# pca10090_sheet4_interface_mcu.net
KiCad netlist of a schematic drawn in Altium Designer
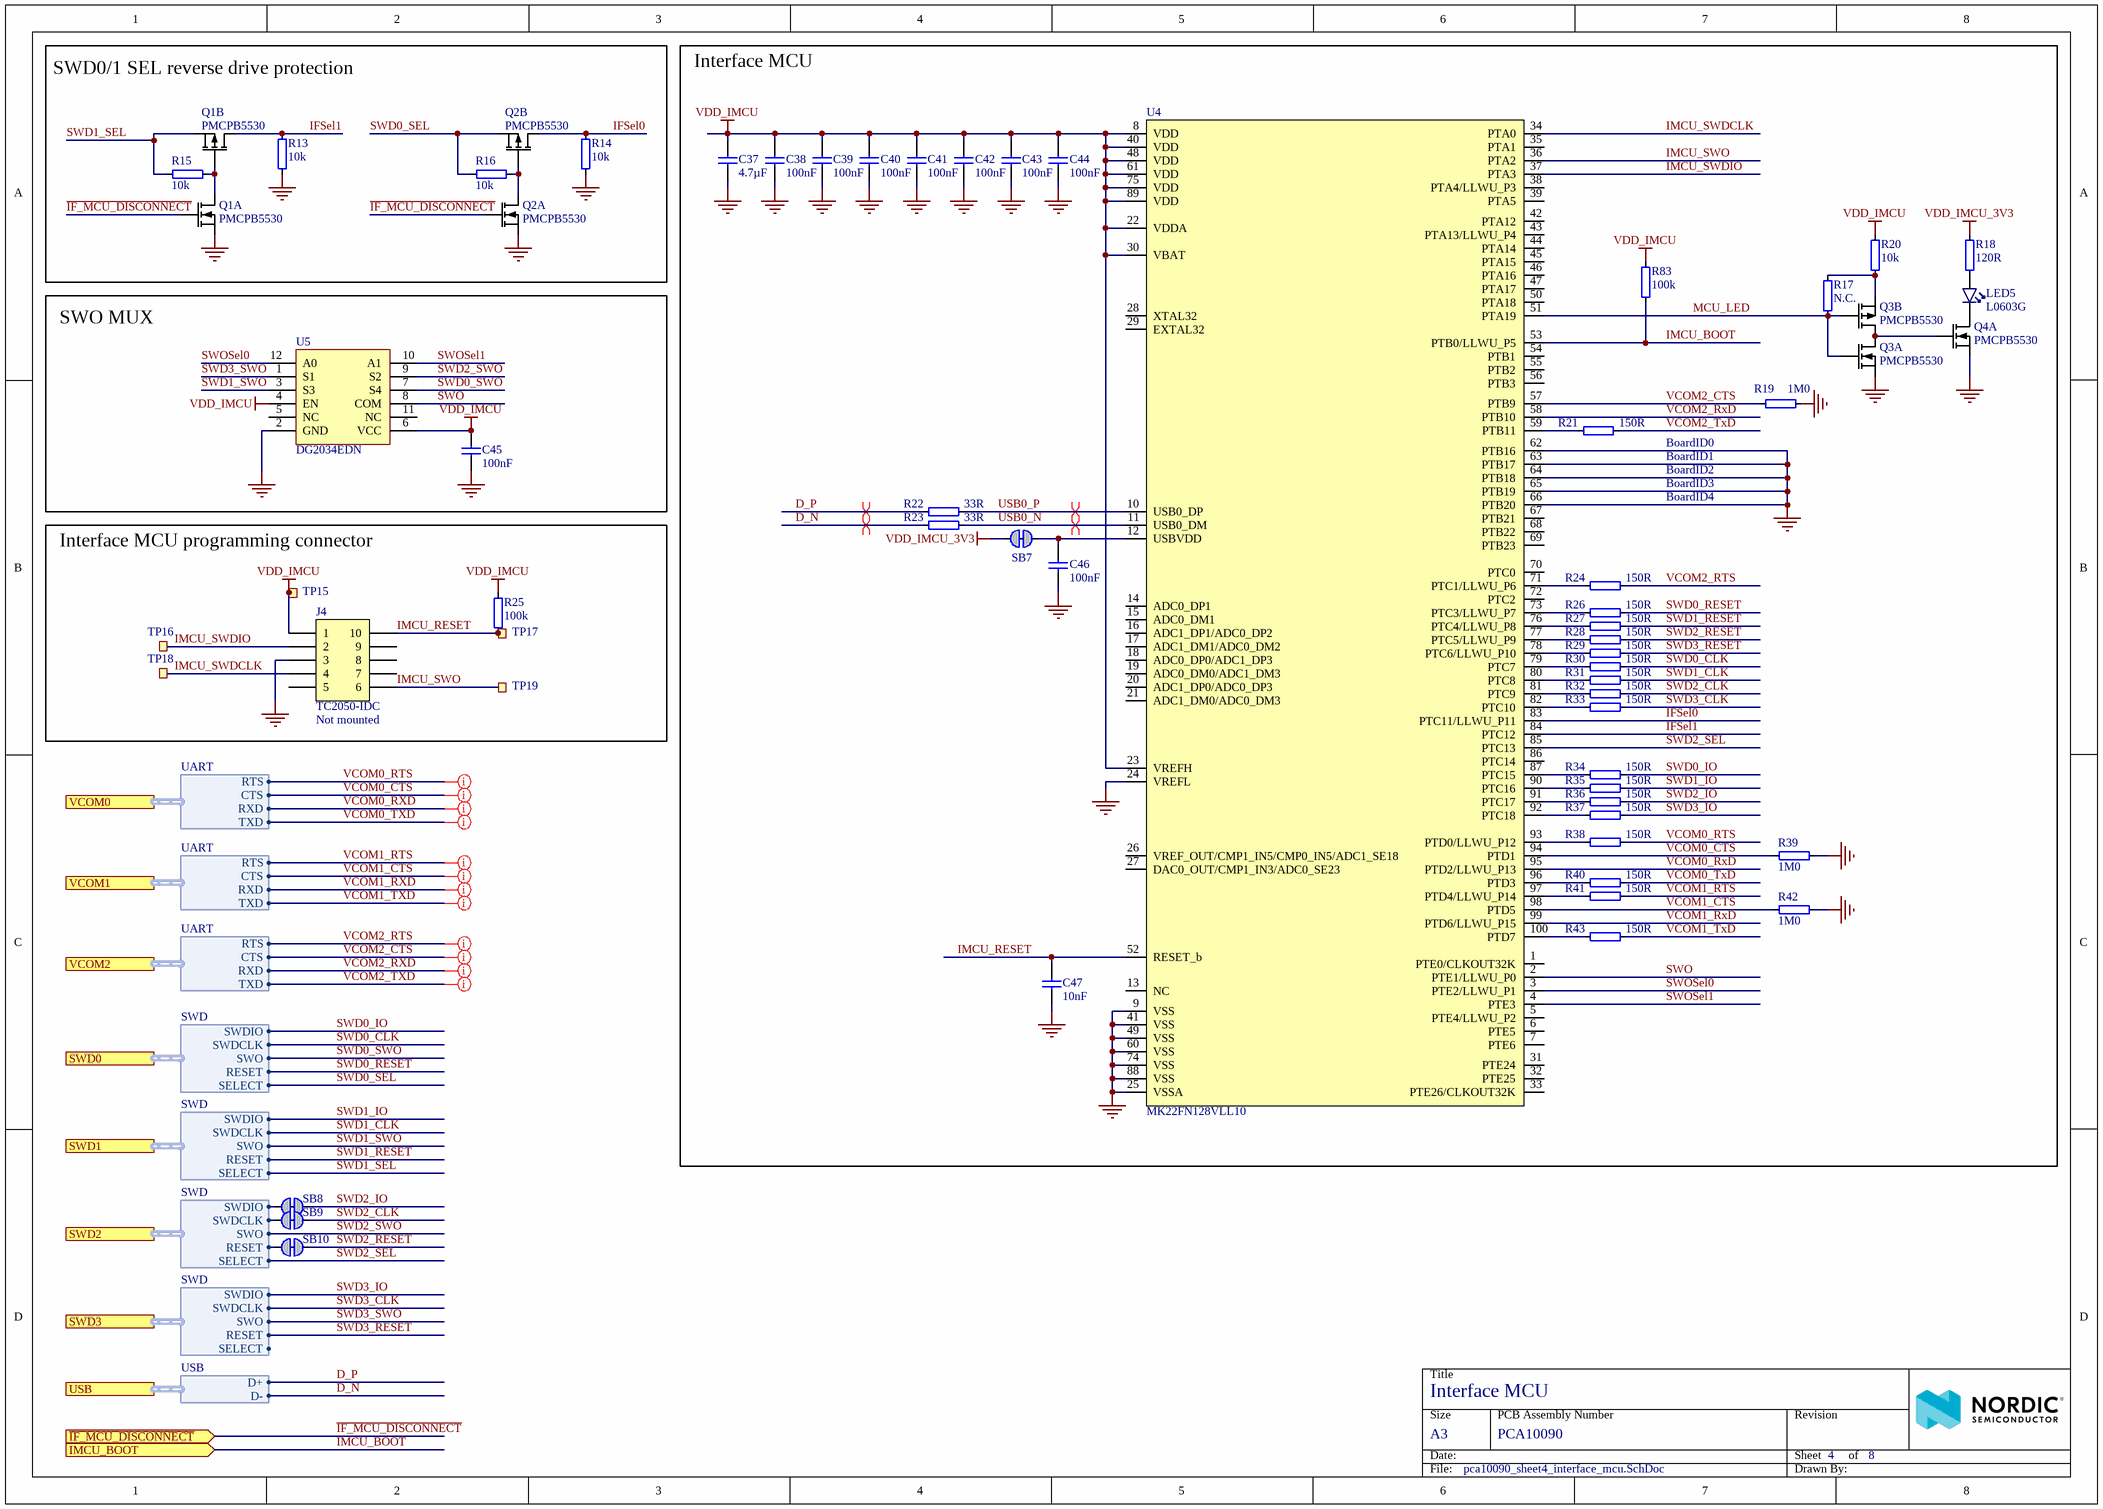
[diagram p0: pca10090_sheet4_interface_mcu.SchDoc]

(export (version "E")
  (design (tool "Eeschema 10.0.6"))
  (components
    (comp (ref "C37")
      (value "4.7µF")
      (footprint "CAPC1005X04L")
      (description "Capacitor, X5R, ±20%")
      (fields
        (field (name "PART NUMBER") "C0402-4µ7")
        (field (name "MANUFACTURER") "N.A.")
        (field (name "AUTHOR") "rsk")
      )
      (libsource (lib "AltiumLib") (part "CAP"))
    )
    (comp (ref "C38")
      (value "100nF")
      (footprint "CAPC0603X03L_C")
      (description "Capacitor, X5R, ±10%")
      (fields
        (field (name "PART NUMBER") "C0201-100n")
        (field (name "MANUFACTURER") "N.A.")
        (field (name "AUTHOR") "rsk")
      )
      (libsource (lib "AltiumLib") (part "CAP"))
    )
    (comp (ref "C39")
      (value "100nF")
      (footprint "CAPC0603X03L_C")
      (description "Capacitor, X5R, ±10%")
      (fields
        (field (name "PART NUMBER") "C0201-100n")
        (field (name "MANUFACTURER") "N.A.")
        (field (name "AUTHOR") "rsk")
      )
      (libsource (lib "AltiumLib") (part "CAP"))
    )
    (comp (ref "C40")
      (value "100nF")
      (footprint "CAPC0603X03L_C")
      (description "Capacitor, X5R, ±10%")
      (fields
        (field (name "PART NUMBER") "C0201-100n")
        (field (name "MANUFACTURER") "N.A.")
        (field (name "AUTHOR") "rsk")
      )
      (libsource (lib "AltiumLib") (part "CAP"))
    )
    (comp (ref "C41")
      (value "100nF")
      (footprint "CAPC0603X03L_C")
      (description "Capacitor, X5R, ±10%")
      (fields
        (field (name "PART NUMBER") "C0201-100n")
        (field (name "MANUFACTURER") "N.A.")
        (field (name "AUTHOR") "rsk")
      )
      (libsource (lib "AltiumLib") (part "CAP"))
    )
    (comp (ref "C42")
      (value "100nF")
      (footprint "CAPC0603X03L_C")
      (description "Capacitor, X5R, ±10%")
      (fields
        (field (name "PART NUMBER") "C0201-100n")
        (field (name "MANUFACTURER") "N.A.")
        (field (name "AUTHOR") "rsk")
      )
      (libsource (lib "AltiumLib") (part "CAP"))
    )
    (comp (ref "C43")
      (value "100nF")
      (footprint "CAPC0603X03L_C")
      (description "Capacitor, X5R, ±10%")
      (fields
        (field (name "PART NUMBER") "C0201-100n")
        (field (name "MANUFACTURER") "N.A.")
        (field (name "AUTHOR") "rsk")
      )
      (libsource (lib "AltiumLib") (part "CAP"))
    )
    (comp (ref "C44")
      (value "100nF")
      (footprint "CAPC0603X03L_C")
      (description "Capacitor, X5R, ±10%")
      (fields
        (field (name "PART NUMBER") "C0201-100n")
        (field (name "MANUFACTURER") "N.A.")
        (field (name "AUTHOR") "rsk")
      )
      (libsource (lib "AltiumLib") (part "CAP"))
    )
    (comp (ref "C45")
      (value "100nF")
      (footprint "CAPC0603X03L_C")
      (description "Capacitor, X5R, ±10%")
      (fields
        (field (name "PART NUMBER") "C0201-100n")
        (field (name "MANUFACTURER") "N.A.")
        (field (name "AUTHOR") "rsk")
      )
      (libsource (lib "AltiumLib") (part "CAP"))
    )
    (comp (ref "C46")
      (value "100nF")
      (footprint "CAPC0603X03L_C")
      (description "Capacitor, X5R, ±10%")
      (fields
        (field (name "PART NUMBER") "C0201-100n")
        (field (name "MANUFACTURER") "N.A.")
        (field (name "AUTHOR") "rsk")
      )
      (libsource (lib "AltiumLib") (part "CAP"))
    )
    (comp (ref "C47")
      (value "10nF")
      (footprint "CAPC0603X03L_C")
      (description "Capacitor, X7R, ±10%")
      (fields
        (field (name "PART NUMBER") "C0201-10n")
        (field (name "MANUFACTURER") "N.A.")
        (field (name "AUTHOR") "rsk")
      )
      (libsource (lib "AltiumLib") (part "CAP"))
    )
    (comp (ref "J4")
      (value "TC2050-IDC")
      (footprint "TC2050-IDC-NLFP")
      (description "CBL PLUG-OF-NAILS 10-PIN")
      (fields
        (field (name "PART NUMBER") "TC2050-IDC-NLFP")
        (field (name "MANUFACTURER") "Tag-Connect LLC")
        (field (name "ASSEMBLY") "Not mounted")
        (field (name "AUTHOR") "rsk")
      )
      (libsource (lib "AltiumLib") (part "CONN-2x5_var2_No_BOM"))
    )
    (comp (ref "LED5")
      (value "L0603G")
      (footprint "LED_0603_G")
      (description "LED, Green, 0603, 573nm, Vf=2.0V, 24mcd, - 40 to +85°C")
      (fields
        (field (name "PART NUMBER") "VS 25C7M5")
        (field (name "MANUFACTURER") "Victory Electronics")
        (field (name "AUTHOR") "rsk")
      )
      (libsource (lib "AltiumLib") (part "D{colon}LED"))
    )
    (comp (ref "Q1")
      (value "PMCPB5530")
      (footprint "PMCPB5530X")
      (description "Mosfet Array N and P-Channel 20V 4A (Ta), 3.4A (Ta) 490mW Surface Mount 6-HUSON-EP (2x2)")
      (fields
        (field (name "PART NUMBER") "PMCPB5530X,115")
        (field (name "MANUFACTURER") "Nexperia")
        (field (name "AUTHOR") "rsk")
      )
      (libsource (lib "AltiumLib") (part "T{colon}FET-N/P-DUAL"))
    )
    (comp (ref "Q2")
      (value "PMCPB5530")
      (footprint "PMCPB5530X")
      (description "Mosfet Array N and P-Channel 20V 4A (Ta), 3.4A (Ta) 490mW Surface Mount 6-HUSON-EP (2x2)")
      (fields
        (field (name "PART NUMBER") "PMCPB5530X,115")
        (field (name "MANUFACTURER") "Nexperia")
        (field (name "AUTHOR") "rsk")
      )
      (libsource (lib "AltiumLib") (part "T{colon}FET-N/P-DUAL"))
    )
    (comp (ref "Q3")
      (value "PMCPB5530")
      (footprint "PMCPB5530X")
      (description "Mosfet Array N and P-Channel 20V 4A (Ta), 3.4A (Ta) 490mW Surface Mount 6-HUSON-EP (2x2)")
      (fields
        (field (name "PART NUMBER") "PMCPB5530X,115")
        (field (name "MANUFACTURER") "Nexperia")
        (field (name "AUTHOR") "rsk")
      )
      (libsource (lib "AltiumLib") (part "T{colon}FET-N/P-DUAL"))
    )
    (comp (ref "Q4")
      (value "PMCPB5530")
      (footprint "PMCPB5530X")
      (description "Mosfet Array N and P-Channel 20V 4A (Ta), 3.4A (Ta) 490mW Surface Mount 6-HUSON-EP (2x2)")
      (fields
        (field (name "PART NUMBER") "PMCPB5530X,115")
        (field (name "MANUFACTURER") "Nexperia")
        (field (name "AUTHOR") "rsk")
      )
      (libsource (lib "AltiumLib") (part "T{colon}FET-N/P-DUAL"))
    )
    (comp (ref "R13")
      (value "10k")
      (footprint "RESC0603X03L_C")
      (description "Resistor, ±1%, 0.05W")
      (fields
        (field (name "PART NUMBER") "R0201-10k")
        (field (name "MANUFACTURER") "N.A.")
        (field (name "AUTHOR") "rsk")
      )
      (libsource (lib "AltiumLib") (part "RES"))
    )
    (comp (ref "R14")
      (value "10k")
      (footprint "RESC0603X03L_C")
      (description "Resistor, ±1%, 0.05W")
      (fields
        (field (name "PART NUMBER") "R0201-10k")
        (field (name "MANUFACTURER") "N.A.")
        (field (name "AUTHOR") "rsk")
      )
      (libsource (lib "AltiumLib") (part "RES"))
    )
    (comp (ref "R15")
      (value "10k")
      (footprint "RESC0603X03L_C")
      (description "Resistor, ±1%, 0.05W")
      (fields
        (field (name "PART NUMBER") "R0201-10k")
        (field (name "MANUFACTURER") "N.A.")
        (field (name "AUTHOR") "rsk")
      )
      (libsource (lib "AltiumLib") (part "RES"))
    )
    (comp (ref "R16")
      (value "10k")
      (footprint "RESC0603X03L_C")
      (description "Resistor, ±1%, 0.05W")
      (fields
        (field (name "PART NUMBER") "R0201-10k")
        (field (name "MANUFACTURER") "N.A.")
        (field (name "AUTHOR") "rsk")
      )
      (libsource (lib "AltiumLib") (part "RES"))
    )
    (comp (ref "R17")
      (value "N.C.")
      (footprint "RESC0603X03L_C_NC")
      (description "Not mounted")
      (fields
        (field (name "PART NUMBER") "R0201-N.C.")
        (field (name "MANUFACTURER") "N.A.")
        (field (name "AUTHOR") "rsk")
      )
      (libsource (lib "AltiumLib") (part "RES"))
    )
    (comp (ref "R18")
      (value "120R")
      (footprint "RESC0603X03L_C")
      (description "Resistor, ±1%, 0.05W")
      (fields
        (field (name "PART NUMBER") "R0201-120")
        (field (name "MANUFACTURER") "N.A.")
        (field (name "AUTHOR") "rsk")
      )
      (libsource (lib "AltiumLib") (part "RES"))
    )
    (comp (ref "R19")
      (value "1M0")
      (footprint "RESC0603X03L_C")
      (description "Resistor, ±1%, 0.05W")
      (fields
        (field (name "PART NUMBER") "R0201-1M0")
        (field (name "MANUFACTURER") "N.A.")
        (field (name "AUTHOR") "rsk")
      )
      (libsource (lib "AltiumLib") (part "RES"))
    )
    (comp (ref "R20")
      (value "10k")
      (footprint "RESC0603X03L_C")
      (description "Resistor, ±1%, 0.05W")
      (fields
        (field (name "PART NUMBER") "R0201-10k")
        (field (name "MANUFACTURER") "N.A.")
        (field (name "AUTHOR") "rsk")
      )
      (libsource (lib "AltiumLib") (part "RES"))
    )
    (comp (ref "R21")
      (value "150R")
      (footprint "RESC0603X03L_C")
      (description "Resistor, ±1%, 0.05W")
      (fields
        (field (name "PART NUMBER") "R0201-150")
        (field (name "MANUFACTURER") "N.A.")
        (field (name "AUTHOR") "rsk")
      )
      (libsource (lib "AltiumLib") (part "RES"))
    )
    (comp (ref "R22")
      (value "33R")
      (footprint "RESC0603X03L_C")
      (description "Resistor, ±1%, 0.05W")
      (fields
        (field (name "PART NUMBER") "R0201-33R")
        (field (name "MANUFACTURER") "N.A.")
        (field (name "AUTHOR") "rsk")
      )
      (libsource (lib "AltiumLib") (part "RES"))
    )
    (comp (ref "R23")
      (value "33R")
      (footprint "RESC0603X03L_C")
      (description "Resistor, ±1%, 0.05W")
      (fields
        (field (name "PART NUMBER") "R0201-33R")
        (field (name "MANUFACTURER") "N.A.")
        (field (name "AUTHOR") "rsk")
      )
      (libsource (lib "AltiumLib") (part "RES"))
    )
    (comp (ref "R24")
      (value "150R")
      (footprint "RESC0603X03L_C")
      (description "Resistor, ±1%, 0.05W")
      (fields
        (field (name "PART NUMBER") "R0201-150")
        (field (name "MANUFACTURER") "N.A.")
        (field (name "AUTHOR") "rsk")
      )
      (libsource (lib "AltiumLib") (part "RES"))
    )
    (comp (ref "R25")
      (value "100k")
      (footprint "RESC0603X03L_C")
      (description "Resistor, ±1%, 0.05W")
      (fields
        (field (name "PART NUMBER") "R0201-100k")
        (field (name "MANUFACTURER") "N.A.")
        (field (name "AUTHOR") "rsk")
      )
      (libsource (lib "AltiumLib") (part "RES"))
    )
    (comp (ref "R26")
      (value "150R")
      (footprint "RESC0603X03L_C")
      (description "Resistor, ±1%, 0.05W")
      (fields
        (field (name "PART NUMBER") "R0201-150")
        (field (name "MANUFACTURER") "N.A.")
        (field (name "AUTHOR") "rsk")
      )
      (libsource (lib "AltiumLib") (part "RES"))
    )
    (comp (ref "R27")
      (value "150R")
      (footprint "RESC0603X03L_C")
      (description "Resistor, ±1%, 0.05W")
      (fields
        (field (name "PART NUMBER") "R0201-150")
        (field (name "MANUFACTURER") "N.A.")
        (field (name "AUTHOR") "rsk")
      )
      (libsource (lib "AltiumLib") (part "RES"))
    )
    (comp (ref "R28")
      (value "150R")
      (footprint "RESC0603X03L_C")
      (description "Resistor, ±1%, 0.05W")
      (fields
        (field (name "PART NUMBER") "R0201-150")
        (field (name "MANUFACTURER") "N.A.")
        (field (name "AUTHOR") "rsk")
      )
      (libsource (lib "AltiumLib") (part "RES"))
    )
    (comp (ref "R29")
      (value "150R")
      (footprint "RESC0603X03L_C")
      (description "Resistor, ±1%, 0.05W")
      (fields
        (field (name "PART NUMBER") "R0201-150")
        (field (name "MANUFACTURER") "N.A.")
        (field (name "AUTHOR") "rsk")
      )
      (libsource (lib "AltiumLib") (part "RES"))
    )
    (comp (ref "R30")
      (value "150R")
      (footprint "RESC0603X03L_C")
      (description "Resistor, ±1%, 0.05W")
      (fields
        (field (name "PART NUMBER") "R0201-150")
        (field (name "MANUFACTURER") "N.A.")
        (field (name "AUTHOR") "rsk")
      )
      (libsource (lib "AltiumLib") (part "RES"))
    )
    (comp (ref "R31")
      (value "150R")
      (footprint "RESC0603X03L_C")
      (description "Resistor, ±1%, 0.05W")
      (fields
        (field (name "PART NUMBER") "R0201-150")
        (field (name "MANUFACTURER") "N.A.")
        (field (name "AUTHOR") "rsk")
      )
      (libsource (lib "AltiumLib") (part "RES"))
    )
    (comp (ref "R32")
      (value "150R")
      (footprint "RESC0603X03L_C")
      (description "Resistor, ±1%, 0.05W")
      (fields
        (field (name "PART NUMBER") "R0201-150")
        (field (name "MANUFACTURER") "N.A.")
        (field (name "AUTHOR") "rsk")
      )
      (libsource (lib "AltiumLib") (part "RES"))
    )
    (comp (ref "R33")
      (value "150R")
      (footprint "RESC0603X03L_C")
      (description "Resistor, ±1%, 0.05W")
      (fields
        (field (name "PART NUMBER") "R0201-150")
        (field (name "MANUFACTURER") "N.A.")
        (field (name "AUTHOR") "rsk")
      )
      (libsource (lib "AltiumLib") (part "RES"))
    )
    (comp (ref "R34")
      (value "150R")
      (footprint "RESC0603X03L_C")
      (description "Resistor, ±1%, 0.05W")
      (fields
        (field (name "PART NUMBER") "R0201-150")
        (field (name "MANUFACTURER") "N.A.")
        (field (name "AUTHOR") "rsk")
      )
      (libsource (lib "AltiumLib") (part "RES"))
    )
    (comp (ref "R35")
      (value "150R")
      (footprint "RESC0603X03L_C")
      (description "Resistor, ±1%, 0.05W")
      (fields
        (field (name "PART NUMBER") "R0201-150")
        (field (name "MANUFACTURER") "N.A.")
        (field (name "AUTHOR") "rsk")
      )
      (libsource (lib "AltiumLib") (part "RES"))
    )
    (comp (ref "R36")
      (value "150R")
      (footprint "RESC0603X03L_C")
      (description "Resistor, ±1%, 0.05W")
      (fields
        (field (name "PART NUMBER") "R0201-150")
        (field (name "MANUFACTURER") "N.A.")
        (field (name "AUTHOR") "rsk")
      )
      (libsource (lib "AltiumLib") (part "RES"))
    )
    (comp (ref "R37")
      (value "150R")
      (footprint "RESC0603X03L_C")
      (description "Resistor, ±1%, 0.05W")
      (fields
        (field (name "PART NUMBER") "R0201-150")
        (field (name "MANUFACTURER") "N.A.")
        (field (name "AUTHOR") "rsk")
      )
      (libsource (lib "AltiumLib") (part "RES"))
    )
    (comp (ref "R38")
      (value "150R")
      (footprint "RESC0603X03L_C")
      (description "Resistor, ±1%, 0.05W")
      (fields
        (field (name "PART NUMBER") "R0201-150")
        (field (name "MANUFACTURER") "N.A.")
        (field (name "AUTHOR") "rsk")
      )
      (libsource (lib "AltiumLib") (part "RES"))
    )
    (comp (ref "R39")
      (value "1M0")
      (footprint "RESC0603X03L_C")
      (description "Resistor, ±1%, 0.05W")
      (fields
        (field (name "PART NUMBER") "R0201-1M0")
        (field (name "MANUFACTURER") "N.A.")
        (field (name "AUTHOR") "rsk")
      )
      (libsource (lib "AltiumLib") (part "RES"))
    )
    (comp (ref "R40")
      (value "150R")
      (footprint "RESC0603X03L_C")
      (description "Resistor, ±1%, 0.05W")
      (fields
        (field (name "PART NUMBER") "R0201-150")
        (field (name "MANUFACTURER") "N.A.")
        (field (name "AUTHOR") "rsk")
      )
      (libsource (lib "AltiumLib") (part "RES"))
    )
    (comp (ref "R41")
      (value "150R")
      (footprint "RESC0603X03L_C")
      (description "Resistor, ±1%, 0.05W")
      (fields
        (field (name "PART NUMBER") "R0201-150")
        (field (name "MANUFACTURER") "N.A.")
        (field (name "AUTHOR") "rsk")
      )
      (libsource (lib "AltiumLib") (part "RES"))
    )
    (comp (ref "R42")
      (value "1M0")
      (footprint "RESC0603X03L_C")
      (description "Resistor, ±1%, 0.05W")
      (fields
        (field (name "PART NUMBER") "R0201-1M0")
        (field (name "MANUFACTURER") "N.A.")
        (field (name "AUTHOR") "rsk")
      )
      (libsource (lib "AltiumLib") (part "RES"))
    )
    (comp (ref "R43")
      (value "150R")
      (footprint "RESC0603X03L_C")
      (description "Resistor, ±1%, 0.05W")
      (fields
        (field (name "PART NUMBER") "R0201-150")
        (field (name "MANUFACTURER") "N.A.")
        (field (name "AUTHOR") "rsk")
      )
      (libsource (lib "AltiumLib") (part "RES"))
    )
    (comp (ref "R83")
      (value "100k")
      (footprint "RESC0603X03L_C")
      (description "Resistor, ±1%, 0.05W")
      (fields
        (field (name "PART NUMBER") "R0201-100k")
        (field (name "MANUFACTURER") "N.A.")
        (field (name "AUTHOR") "rsk")
      )
      (libsource (lib "AltiumLib") (part "RES"))
    )
    (comp (ref "SB7")
      (value "Solderbridge")
      (footprint "Solderbridge_Shorted")
      (description "Shorted Solderbridge")
      (fields
        (field (name "PART NUMBER") "Solderbridge Shorted")
        (field (name "MANUFACTURER") "N.A.")
        (field (name "AUTHOR") "rsk")
      )
      (libsource (lib "AltiumLib") (part "SOLDERBRIDGE_SHORTED"))
    )
    (comp (ref "SB8")
      (value "Solderbridge")
      (footprint "Solderbridge_Shorted")
      (description "Shorted Solderbridge")
      (fields
        (field (name "PART NUMBER") "Solderbridge Shorted")
        (field (name "MANUFACTURER") "N.A.")
        (field (name "AUTHOR") "rsk")
      )
      (libsource (lib "AltiumLib") (part "SOLDERBRIDGE_SHORTED"))
    )
    (comp (ref "SB9")
      (value "Solderbridge")
      (footprint "Solderbridge_Shorted")
      (description "Shorted Solderbridge")
      (fields
        (field (name "PART NUMBER") "Solderbridge Shorted")
        (field (name "MANUFACTURER") "N.A.")
        (field (name "AUTHOR") "rsk")
      )
      (libsource (lib "AltiumLib") (part "SOLDERBRIDGE_SHORTED"))
    )
    (comp (ref "SB10")
      (value "Solderbridge")
      (footprint "Solderbridge_Shorted")
      (description "Shorted Solderbridge")
      (fields
        (field (name "PART NUMBER") "Solderbridge Shorted")
        (field (name "MANUFACTURER") "N.A.")
        (field (name "AUTHOR") "rsk")
      )
      (libsource (lib "AltiumLib") (part "SOLDERBRIDGE_SHORTED"))
    )
    (comp (ref "TP15")
      (value "Ø1.5mm,SMD")
      (footprint "TP_SMD_D1.5mm")
      (description "1.5mm circular SMD testpad")
      (fields
        (field (name "PART NUMBER") "TP_SMD_Ø1.5MM")
        (field (name "MANUFACTURER") "Nordic Semiconductor")
        (field (name "AUTHOR") "rsk")
      )
      (libsource (lib "AltiumLib") (part "TESTPAD"))
    )
    (comp (ref "TP16")
      (value "Ø1.5mm,SMD")
      (footprint "TP_SMD_D1.5mm")
      (description "1.5mm circular SMD testpad")
      (fields
        (field (name "PART NUMBER") "TP_SMD_Ø1.5MM")
        (field (name "MANUFACTURER") "Nordic Semiconductor")
        (field (name "AUTHOR") "rsk")
      )
      (libsource (lib "") (part "TESTPAD_1"))
    )
    (comp (ref "TP17")
      (value "Ø1.5mm,SMD")
      (footprint "TP_SMD_D1.5mm")
      (description "1.5mm circular SMD testpad")
      (fields
        (field (name "PART NUMBER") "TP_SMD_Ø1.5MM")
        (field (name "MANUFACTURER") "Nordic Semiconductor")
        (field (name "AUTHOR") "rsk")
      )
      (libsource (lib "AltiumLib") (part "TESTPAD"))
    )
    (comp (ref "TP18")
      (value "Ø1.5mm,SMD")
      (footprint "TP_SMD_D1.5mm")
      (description "1.5mm circular SMD testpad")
      (fields
        (field (name "PART NUMBER") "TP_SMD_Ø1.5MM")
        (field (name "MANUFACTURER") "Nordic Semiconductor")
        (field (name "AUTHOR") "rsk")
      )
      (libsource (lib "") (part "TESTPAD_1"))
    )
    (comp (ref "TP19")
      (value "Ø1.5mm,SMD")
      (footprint "TP_SMD_D1.5mm")
      (description "1.5mm circular SMD testpad")
      (fields
        (field (name "PART NUMBER") "TP_SMD_Ø1.5MM")
        (field (name "MANUFACTURER") "Nordic Semiconductor")
        (field (name "AUTHOR") "rsk")
      )
      (libsource (lib "AltiumLib") (part "TESTPAD"))
    )
    (comp (ref "U4")
      (value "MK22FN128VLL10")
      (footprint "TSQFP50P1600X1600X160-100N")
      (description "100MHz Cortex-M4F Performance MCU, 128kB Flash, 24kB SRAM, Full-Speed USB")
      (fields (field (name "MANUFACTURER") "NXP Semiconductors") (field (name "AUTHOR") "rsk"))
      (libsource (lib "AltiumLib") (part "MK22FN128VLL10"))
    )
    (comp (ref "U5")
      (value "DG2034EDN")
      (footprint "DG2034EDN")
      (description "POWER DOWN FAULT PROTECTED,1.8VT")
      (fields
        (field (name "MANUFACTURER") "Vishay")
        (field (name "MANUFACTURER PART NUMBER") "DG2034EDN-T1-GE4")
        (field (name "AUTHOR") "rsk")
      )
      (libsource (lib "AltiumLib") (part "DG2034EDN"))
    )
  )
  (nets
    (net (code "4") (name "/D_N") (class "Default")
      (node (ref "R23") (pin "1") (pinfunction "1_1") (pintype "passive"))
    )
    (net (code "5") (name "/D_P") (class "Default")
      (node (ref "R22") (pin "1") (pinfunction "1_1") (pintype "passive"))
    )
    (net (code "6") (name "/IFSel0") (class "Default")
      (node (ref "Q2") (pin "3") (pinfunction "D2_3") (pintype "passive"))
      (node (ref "R14") (pin "1") (pinfunction "1_1") (pintype "passive"))
      (node (ref "U4") (pin "83") (pinfunction "PTC11/LLWU_P11_83") (pintype "passive"))
    )
    (net (code "7") (name "/IFSel1") (class "Default")
      (node (ref "Q1") (pin "3") (pinfunction "D2_3") (pintype "passive"))
      (node (ref "R13") (pin "2") (pinfunction "2_2") (pintype "passive"))
      (node (ref "U4") (pin "84") (pinfunction "PTC12_84") (pintype "passive"))
    )
    (net (code "8") (name "/IMCU_BOOT") (class "Default")
      (node (ref "R83") (pin "1") (pinfunction "1_1") (pintype "passive"))
      (node (ref "U4") (pin "53") (pinfunction "PTB0/LLWU_P5_53") (pintype "passive"))
    )
    (net (code "9") (name "/IMCU_RESET") (class "Default")
      (node (ref "C47") (pin "2") (pinfunction "2_2") (pintype "passive"))
      (node (ref "J4") (pin "10") (pinfunction "10_10") (pintype "passive"))
      (node (ref "R25") (pin "1") (pinfunction "1_1") (pintype "passive"))
      (node (ref "TP17") (pin "1") (pinfunction "1_1") (pintype "passive"))
      (node (ref "U4") (pin "52") (pinfunction "RESET_b_52") (pintype "passive"))
    )
    (net (code "10") (name "/IMCU_SWDCLK") (class "Default")
      (node (ref "J4") (pin "4") (pinfunction "4_4") (pintype "passive"))
      (node (ref "TP18") (pin "1") (pinfunction "1_1") (pintype "passive"))
      (node (ref "U4") (pin "34") (pinfunction "PTA0_34") (pintype "passive"))
    )
    (net (code "11") (name "/IMCU_SWDIO") (class "Default")
      (node (ref "J4") (pin "2") (pinfunction "2_2") (pintype "passive"))
      (node (ref "TP16") (pin "1") (pinfunction "1_1") (pintype "passive"))
      (node (ref "U4") (pin "37") (pinfunction "PTA3_37") (pintype "passive"))
    )
    (net (code "12") (name "/IMCU_SWO") (class "Default")
      (node (ref "J4") (pin "6") (pinfunction "6_6") (pintype "passive"))
      (node (ref "TP19") (pin "1") (pinfunction "1_1") (pintype "passive"))
      (node (ref "U4") (pin "36") (pinfunction "PTA2_36") (pintype "passive"))
    )
    (net (code "13") (name "/MCU_LED") (class "Default")
      (node (ref "Q3") (pin "2") (pinfunction "G1_2") (pintype "passive"))
      (node (ref "Q3") (pin "5") (pinfunction "G2_5") (pintype "passive"))
      (node (ref "R17") (pin "1") (pinfunction "1_1") (pintype "passive"))
      (node (ref "U4") (pin "51") (pinfunction "PTA19_51") (pintype "passive"))
    )
    (net (code "14") (name "/SWD0_CLK") (class "Default")
      (node (ref "R30") (pin "2") (pinfunction "2_2") (pintype "passive"))
    )
    (net (code "15") (name "/SWD0_IO") (class "Default")
      (node (ref "R34") (pin "2") (pinfunction "2_2") (pintype "passive"))
    )
    (net (code "16") (name "/SWD0_RESET") (class "Default")
      (node (ref "R26") (pin "2") (pinfunction "2_2") (pintype "passive"))
    )
    (net (code "17") (name "/SWD0_SEL") (class "Default")
      (node (ref "Q2") (pin "4") (pinfunction "S2_4") (pintype "passive"))
      (node (ref "R16") (pin "2") (pinfunction "2_2") (pintype "passive"))
    )
    (net (code "18") (name "/SWD0_SWO") (class "Default")
      (node (ref "U5") (pin "7") (pinfunction "S4_7") (pintype "passive"))
    )
    (net (code "19") (name "/SWD1_CLK") (class "Default")
      (node (ref "R31") (pin "2") (pinfunction "2_2") (pintype "passive"))
    )
    (net (code "20") (name "/SWD1_IO") (class "Default")
      (node (ref "R35") (pin "2") (pinfunction "2_2") (pintype "passive"))
    )
    (net (code "21") (name "/SWD1_RESET") (class "Default")
      (node (ref "R27") (pin "2") (pinfunction "2_2") (pintype "passive"))
    )
    (net (code "22") (name "/SWD1_SEL") (class "Default")
      (node (ref "Q1") (pin "4") (pinfunction "S2_4") (pintype "passive"))
      (node (ref "R15") (pin "1") (pinfunction "1_1") (pintype "passive"))
    )
    (net (code "23") (name "/SWD1_SWO") (class "Default")
      (node (ref "U5") (pin "3") (pinfunction "S3_3") (pintype "power_in"))
    )
    (net (code "24") (name "/SWD2_CLK") (class "Default")
      (node (ref "R32") (pin "2") (pinfunction "2_2") (pintype "passive"))
      (node (ref "SB9") (pin "2") (pinfunction "1_2") (pintype "passive"))
    )
    (net (code "25") (name "/SWD2_IO") (class "Default")
      (node (ref "R36") (pin "2") (pinfunction "2_2") (pintype "passive"))
      (node (ref "SB8") (pin "2") (pinfunction "1_2") (pintype "passive"))
    )
    (net (code "26") (name "/SWD2_RESET") (class "Default")
      (node (ref "R28") (pin "2") (pinfunction "2_2") (pintype "passive"))
      (node (ref "SB10") (pin "2") (pinfunction "1_2") (pintype "passive"))
    )
    (net (code "27") (name "/SWD2_SEL") (class "Default")
      (node (ref "U4") (pin "85") (pinfunction "PTC13_85") (pintype "passive"))
    )
    (net (code "28") (name "/SWD2_SWO") (class "Default")
      (node (ref "U5") (pin "9") (pinfunction "S2_9") (pintype "passive"))
    )
    (net (code "29") (name "/SWD3_CLK") (class "Default")
      (node (ref "R33") (pin "2") (pinfunction "2_2") (pintype "passive"))
    )
    (net (code "30") (name "/SWD3_IO") (class "Default")
      (node (ref "R37") (pin "2") (pinfunction "2_2") (pintype "passive"))
    )
    (net (code "31") (name "/SWD3_RESET") (class "Default")
      (node (ref "R29") (pin "2") (pinfunction "2_2") (pintype "passive"))
    )
    (net (code "32") (name "/SWD3_SWO") (class "Default")
      (node (ref "U5") (pin "1") (pinfunction "S1_1") (pintype "passive"))
    )
    (net (code "33") (name "/SWO") (class "Default")
      (node (ref "U4") (pin "2") (pinfunction "PTE1/LLWU_P0_2") (pintype "passive"))
      (node (ref "U5") (pin "8") (pinfunction "COM_8") (pintype "passive"))
    )
    (net (code "34") (name "/SWOSel0") (class "Default")
      (node (ref "U4") (pin "3") (pinfunction "PTE2/LLWU_P1_3") (pintype "passive"))
      (node (ref "U5") (pin "12") (pinfunction "A0_12") (pintype "passive"))
    )
    (net (code "35") (name "/SWOSel1") (class "Default")
      (node (ref "U4") (pin "4") (pinfunction "PTE3_4") (pintype "passive"))
      (node (ref "U5") (pin "10") (pinfunction "A1_10") (pintype "passive"))
    )
    (net (code "36") (name "/USB0_N") (class "Default")
      (node (ref "R23") (pin "2") (pinfunction "2_2") (pintype "passive"))
      (node (ref "U4") (pin "11") (pinfunction "USB0_DM_11") (pintype "passive"))
    )
    (net (code "37") (name "/USB0_P") (class "Default")
      (node (ref "R22") (pin "2") (pinfunction "2_2") (pintype "passive"))
      (node (ref "U4") (pin "10") (pinfunction "USB0_DP_10") (pintype "passive"))
    )
    (net (code "38") (name "/VCOM0_CTS") (class "Default")
      (node (ref "R39") (pin "1") (pinfunction "1_1") (pintype "passive"))
      (node (ref "U4") (pin "94") (pinfunction "PTD1_94") (pintype "passive"))
    )
    (net (code "39") (name "/VCOM0_RTS") (class "Default")
      (node (ref "R38") (pin "2") (pinfunction "2_2") (pintype "passive"))
    )
    (net (code "41") (name "/VCOM0_RxD") (class "Default")
      (node (ref "U4") (pin "95") (pinfunction "PTD2/LLWU_P13_95") (pintype "passive"))
    )
    (net (code "43") (name "/VCOM0_TxD") (class "Default")
      (node (ref "R40") (pin "2") (pinfunction "2_2") (pintype "passive"))
    )
    (net (code "44") (name "/VCOM1_CTS") (class "Default")
      (node (ref "R42") (pin "1") (pinfunction "1_1") (pintype "passive"))
      (node (ref "U4") (pin "98") (pinfunction "PTD5_98") (pintype "passive"))
    )
    (net (code "45") (name "/VCOM1_RTS") (class "Default")
      (node (ref "R41") (pin "2") (pinfunction "2_2") (pintype "passive"))
    )
    (net (code "47") (name "/VCOM1_RxD") (class "Default")
      (node (ref "U4") (pin "99") (pinfunction "PTD6/LLWU_P15_99") (pintype "passive"))
    )
    (net (code "49") (name "/VCOM1_TxD") (class "Default")
      (node (ref "R43") (pin "2") (pinfunction "2_2") (pintype "passive"))
    )
    (net (code "50") (name "/VCOM2_CTS") (class "Default")
      (node (ref "R19") (pin "1") (pinfunction "1_1") (pintype "passive"))
      (node (ref "U4") (pin "57") (pinfunction "PTB9_57") (pintype "passive"))
    )
    (net (code "51") (name "/VCOM2_RTS") (class "Default")
      (node (ref "R24") (pin "2") (pinfunction "2_2") (pintype "passive"))
    )
    (net (code "53") (name "/VCOM2_RxD") (class "Default")
      (node (ref "U4") (pin "58") (pinfunction "PTB10_58") (pintype "passive"))
    )
    (net (code "55") (name "/VCOM2_TxD") (class "Default")
      (node (ref "R21") (pin "2") (pinfunction "2_2") (pintype "passive"))
    )
    (net (code "59") (name "/~{IF_MCU_DISCONNECT}") (class "Default")
      (node (ref "Q1") (pin "2") (pinfunction "G1_2") (pintype "passive"))
      (node (ref "Q2") (pin "2") (pinfunction "G1_2") (pintype "passive"))
    )
    (net (code "60") (name "GND") (class "Default")
      (node (ref "C37") (pin "2") (pinfunction "2_2") (pintype "passive"))
      (node (ref "C38") (pin "1") (pinfunction "1_1") (pintype "passive"))
      (node (ref "C39") (pin "1") (pinfunction "1_1") (pintype "passive"))
      (node (ref "C40") (pin "2") (pinfunction "2_2") (pintype "passive"))
      (node (ref "C41") (pin "1") (pinfunction "1_1") (pintype "passive"))
      (node (ref "C42") (pin "1") (pinfunction "1_1") (pintype "passive"))
      (node (ref "C43") (pin "1") (pinfunction "1_1") (pintype "passive"))
      (node (ref "C44") (pin "1") (pinfunction "1_1") (pintype "passive"))
      (node (ref "C45") (pin "2") (pinfunction "2_2") (pintype "passive"))
      (node (ref "C46") (pin "2") (pinfunction "2_2") (pintype "passive"))
      (node (ref "C47") (pin "1") (pinfunction "1_1") (pintype "passive"))
      (node (ref "J4") (pin "3") (pinfunction "3_3") (pintype "passive"))
      (node (ref "Q1") (pin "1") (pinfunction "S1_1") (pintype "passive"))
      (node (ref "Q2") (pin "1") (pinfunction "S1_1") (pintype "passive"))
      (node (ref "Q3") (pin "1") (pinfunction "S1_1") (pintype "passive"))
      (node (ref "Q4") (pin "1") (pinfunction "S1_1") (pintype "passive"))
      (node (ref "R13") (pin "1") (pinfunction "1_1") (pintype "passive"))
      (node (ref "R14") (pin "2") (pinfunction "2_2") (pintype "passive"))
      (node (ref "R19") (pin "2") (pinfunction "2_2") (pintype "passive"))
      (node (ref "R39") (pin "2") (pinfunction "2_2") (pintype "passive"))
      (node (ref "R42") (pin "2") (pinfunction "2_2") (pintype "passive"))
      (node (ref "U4") (pin "24") (pinfunction "VREFL_24") (pintype "passive"))
      (node (ref "U4") (pin "25") (pinfunction "VSSA_25") (pintype "passive"))
      (node (ref "U4") (pin "41") (pinfunction "VSS_41") (pintype "passive"))
      (node (ref "U4") (pin "49") (pinfunction "VSS_49") (pintype "passive"))
      (node (ref "U4") (pin "60") (pinfunction "VSS_60") (pintype "passive"))
      (node (ref "U4") (pin "62") (pinfunction "PTB16_62") (pintype "passive"))
      (node (ref "U4") (pin "63") (pinfunction "PTB17_63") (pintype "passive"))
      (node (ref "U4") (pin "64") (pinfunction "PTB18_64") (pintype "passive"))
      (node (ref "U4") (pin "65") (pinfunction "PTB19_65") (pintype "passive"))
      (node (ref "U4") (pin "66") (pinfunction "PTB20_66") (pintype "passive"))
      (node (ref "U4") (pin "74") (pinfunction "VSS_74") (pintype "passive"))
      (node (ref "U4") (pin "88") (pinfunction "VSS_88") (pintype "passive"))
      (node (ref "U4") (pin "9") (pinfunction "VSS_9") (pintype "passive"))
      (node (ref "U5") (pin "2") (pinfunction "GND_2") (pintype "passive"))
    )
    (net (code "61") (name "Net-(LED5-A)") (class "Default")
      (node (ref "LED5") (pin "2") (pinfunction "A_2") (pintype "passive"))
      (node (ref "R18") (pin "1") (pinfunction "1_1") (pintype "passive"))
    )
    (net (code "62") (name "Net-(LED5-C)") (class "Default")
      (node (ref "LED5") (pin "1") (pinfunction "C_1") (pintype "passive"))
      (node (ref "Q4") (pin "6") (pinfunction "D1_6") (pintype "passive"))
    )
    (net (code "63") (name "Net-(Q1A-D1)") (class "Default")
      (node (ref "Q1") (pin "5") (pinfunction "G2_5") (pintype "passive"))
      (node (ref "Q1") (pin "6") (pinfunction "D1_6") (pintype "passive"))
      (node (ref "R15") (pin "2") (pinfunction "2_2") (pintype "passive"))
    )
    (net (code "64") (name "Net-(Q2A-D1)") (class "Default")
      (node (ref "Q2") (pin "5") (pinfunction "G2_5") (pintype "passive"))
      (node (ref "Q2") (pin "6") (pinfunction "D1_6") (pintype "passive"))
      (node (ref "R16") (pin "1") (pinfunction "1_1") (pintype "passive"))
    )
    (net (code "65") (name "Net-(Q3A-D1)") (class "Default")
      (node (ref "Q3") (pin "3") (pinfunction "D2_3") (pintype "passive"))
      (node (ref "Q3") (pin "6") (pinfunction "D1_6") (pintype "passive"))
      (node (ref "Q4") (pin "2") (pinfunction "G1_2") (pintype "passive"))
    )
    (net (code "66") (name "Net-(Q3B-S2)") (class "Default")
      (node (ref "Q3") (pin "4") (pinfunction "S2_4") (pintype "passive"))
      (node (ref "R17") (pin "2") (pinfunction "2_2") (pintype "passive"))
      (node (ref "R20") (pin "2") (pinfunction "2_2") (pintype "passive"))
    )
    (net (code "67") (name "Net-(SB7-0)") (class "Default")
      (node (ref "C46") (pin "1") (pinfunction "1_1") (pintype "passive"))
      (node (ref "SB7") (pin "1") (pinfunction "0_1") (pintype "passive"))
      (node (ref "U4") (pin "12") (pinfunction "USBVDD_12") (pintype "passive"))
    )
    (net (code "68") (name "Net-(U4-PTB11)") (class "Default")
      (node (ref "R21") (pin "1") (pinfunction "1_1") (pintype "passive"))
      (node (ref "U4") (pin "59") (pinfunction "PTB11_59") (pintype "passive"))
    )
    (net (code "69") (name "Net-(U4-PTC1{slash}LLWU_P6)") (class "Default")
      (node (ref "R24") (pin "1") (pinfunction "1_1") (pintype "passive"))
      (node (ref "U4") (pin "71") (pinfunction "PTC1/LLWU_P6_71") (pintype "passive"))
    )
    (net (code "70") (name "Net-(U4-PTC3{slash}LLWU_P7)") (class "Default")
      (node (ref "R26") (pin "1") (pinfunction "1_1") (pintype "passive"))
      (node (ref "U4") (pin "73") (pinfunction "PTC3/LLWU_P7_73") (pintype "passive"))
    )
    (net (code "71") (name "Net-(U4-PTC4{slash}LLWU_P8)") (class "Default")
      (node (ref "R27") (pin "1") (pinfunction "1_1") (pintype "passive"))
      (node (ref "U4") (pin "76") (pinfunction "PTC4/LLWU_P8_76") (pintype "passive"))
    )
    (net (code "72") (name "Net-(U4-PTC5{slash}LLWU_P9)") (class "Default")
      (node (ref "R28") (pin "1") (pinfunction "1_1") (pintype "passive"))
      (node (ref "U4") (pin "77") (pinfunction "PTC5/LLWU_P9_77") (pintype "passive"))
    )
    (net (code "73") (name "Net-(U4-PTC6{slash}LLWU_P10)") (class "Default")
      (node (ref "R29") (pin "1") (pinfunction "1_1") (pintype "passive"))
      (node (ref "U4") (pin "78") (pinfunction "PTC6/LLWU_P10_78") (pintype "passive"))
    )
    (net (code "74") (name "Net-(U4-PTC7)") (class "Default")
      (node (ref "R30") (pin "1") (pinfunction "1_1") (pintype "passive"))
      (node (ref "U4") (pin "79") (pinfunction "PTC7_79") (pintype "passive"))
    )
    (net (code "75") (name "Net-(U4-PTC8)") (class "Default")
      (node (ref "R31") (pin "1") (pinfunction "1_1") (pintype "passive"))
      (node (ref "U4") (pin "80") (pinfunction "PTC8_80") (pintype "passive"))
    )
    (net (code "76") (name "Net-(U4-PTC9)") (class "Default")
      (node (ref "R32") (pin "1") (pinfunction "1_1") (pintype "passive"))
      (node (ref "U4") (pin "81") (pinfunction "PTC9_81") (pintype "passive"))
    )
    (net (code "77") (name "Net-(U4-PTC10)") (class "Default")
      (node (ref "R33") (pin "1") (pinfunction "1_1") (pintype "passive"))
      (node (ref "U4") (pin "82") (pinfunction "PTC10_82") (pintype "passive"))
    )
    (net (code "78") (name "Net-(U4-PTC15)") (class "Default")
      (node (ref "R34") (pin "1") (pinfunction "1_1") (pintype "passive"))
      (node (ref "U4") (pin "87") (pinfunction "PTC15_87") (pintype "passive"))
    )
    (net (code "79") (name "Net-(U4-PTC16)") (class "Default")
      (node (ref "R35") (pin "1") (pinfunction "1_1") (pintype "passive"))
      (node (ref "U4") (pin "90") (pinfunction "PTC16_90") (pintype "passive"))
    )
    (net (code "80") (name "Net-(U4-PTC17)") (class "Default")
      (node (ref "R36") (pin "1") (pinfunction "1_1") (pintype "passive"))
      (node (ref "U4") (pin "91") (pinfunction "PTC17_91") (pintype "passive"))
    )
    (net (code "81") (name "Net-(U4-PTC18)") (class "Default")
      (node (ref "R37") (pin "1") (pinfunction "1_1") (pintype "passive"))
      (node (ref "U4") (pin "92") (pinfunction "PTC18_92") (pintype "passive"))
    )
    (net (code "82") (name "Net-(U4-PTD0{slash}LLWU_P12)") (class "Default")
      (node (ref "R38") (pin "1") (pinfunction "1_1") (pintype "passive"))
      (node (ref "U4") (pin "93") (pinfunction "PTD0/LLWU_P12_93") (pintype "passive"))
    )
    (net (code "83") (name "Net-(U4-PTD3)") (class "Default")
      (node (ref "R40") (pin "1") (pinfunction "1_1") (pintype "passive"))
      (node (ref "U4") (pin "96") (pinfunction "PTD3_96") (pintype "passive"))
    )
    (net (code "84") (name "Net-(U4-PTD4{slash}LLWU_P14)") (class "Default")
      (node (ref "R41") (pin "1") (pinfunction "1_1") (pintype "passive"))
      (node (ref "U4") (pin "97") (pinfunction "PTD4/LLWU_P14_97") (pintype "passive"))
    )
    (net (code "85") (name "Net-(U4-PTD7)") (class "Default")
      (node (ref "R43") (pin "1") (pinfunction "1_1") (pintype "passive"))
      (node (ref "U4") (pin "100") (pinfunction "PTD7_100") (pintype "passive"))
    )
    (net (code "86") (name "VDD_IMCU") (class "Default")
      (node (ref "C37") (pin "1") (pinfunction "1_1") (pintype "passive"))
      (node (ref "C38") (pin "2") (pinfunction "2_2") (pintype "passive"))
      (node (ref "C39") (pin "2") (pinfunction "2_2") (pintype "passive"))
      (node (ref "C40") (pin "1") (pinfunction "1_1") (pintype "passive"))
      (node (ref "C41") (pin "2") (pinfunction "2_2") (pintype "passive"))
      (node (ref "C42") (pin "2") (pinfunction "2_2") (pintype "passive"))
      (node (ref "C43") (pin "2") (pinfunction "2_2") (pintype "passive"))
      (node (ref "C44") (pin "2") (pinfunction "2_2") (pintype "passive"))
      (node (ref "C45") (pin "1") (pinfunction "1_1") (pintype "passive"))
      (node (ref "J4") (pin "1") (pinfunction "1_1") (pintype "passive"))
      (node (ref "R20") (pin "1") (pinfunction "1_1") (pintype "passive"))
      (node (ref "R25") (pin "2") (pinfunction "2_2") (pintype "passive"))
      (node (ref "R83") (pin "2") (pinfunction "2_2") (pintype "passive"))
      (node (ref "TP15") (pin "1") (pinfunction "1_1") (pintype "passive"))
      (node (ref "U4") (pin "22") (pinfunction "VDDA_22") (pintype "passive"))
      (node (ref "U4") (pin "23") (pinfunction "VREFH_23") (pintype "passive"))
      (node (ref "U4") (pin "30") (pinfunction "VBAT_30") (pintype "passive"))
      (node (ref "U4") (pin "40") (pinfunction "VDD_40") (pintype "passive"))
      (node (ref "U4") (pin "48") (pinfunction "VDD_48") (pintype "passive"))
      (node (ref "U4") (pin "61") (pinfunction "VDD_61") (pintype "passive"))
      (node (ref "U4") (pin "75") (pinfunction "VDD_75") (pintype "passive"))
      (node (ref "U4") (pin "8") (pinfunction "VDD_8") (pintype "passive"))
      (node (ref "U4") (pin "89") (pinfunction "VDD_89") (pintype "passive"))
      (node (ref "U5") (pin "4") (pinfunction "EN_4") (pintype "passive"))
      (node (ref "U5") (pin "6") (pinfunction "VCC_6") (pintype "power_in"))
    )
    (net (code "87") (name "VDD_IMCU_3V3") (class "Default")
      (node (ref "R18") (pin "2") (pinfunction "2_2") (pintype "passive"))
      (node (ref "SB7") (pin "2") (pinfunction "1_2") (pintype "passive"))
    )
    (net (code "88") (name "unconnected-(J4-Pad5)") (class "Default")
      (node (ref "J4") (pin "5") (pinfunction "5_5") (pintype "passive"))
    )
    (net (code "89") (name "unconnected-(J4-Pad7)") (class "Default")
      (node (ref "J4") (pin "7") (pinfunction "7_7") (pintype "passive"))
    )
    (net (code "90") (name "unconnected-(J4-Pad8)") (class "Default")
      (node (ref "J4") (pin "8") (pinfunction "8_8") (pintype "passive"))
    )
    (net (code "91") (name "unconnected-(J4-Pad9)") (class "Default")
      (node (ref "J4") (pin "9") (pinfunction "9_9") (pintype "passive"))
    )
    (net (code "92") (name "unconnected-(SB8-0-Pad1)") (class "Default")
      (node (ref "SB8") (pin "1") (pinfunction "0_1") (pintype "passive"))
    )
    (net (code "93") (name "unconnected-(SB9-0-Pad1)") (class "Default")
      (node (ref "SB9") (pin "1") (pinfunction "0_1") (pintype "passive"))
    )
    (net (code "94") (name "unconnected-(SB10-0-Pad1)") (class "Default")
      (node (ref "SB10") (pin "1") (pinfunction "0_1") (pintype "passive"))
    )
    (net (code "95") (name "unconnected-(U4-ADC0_DM0{slash}ADC1_DM3-Pad19)") (class "Default")
      (node (ref "U4") (pin "19") (pinfunction "ADC0_DM0/ADC1_DM3_19") (pintype "passive"))
    )
    (net (code "96") (name "unconnected-(U4-ADC0_DM1-Pad15)") (class "Default")
      (node (ref "U4") (pin "15") (pinfunction "ADC0_DM1_15") (pintype "passive"))
    )
    (net (code "97") (name "unconnected-(U4-ADC0_DP0{slash}ADC1_DP3-Pad18)") (class "Default")
      (node (ref "U4") (pin "18") (pinfunction "ADC0_DP0/ADC1_DP3_18") (pintype "passive"))
    )
    (net (code "98") (name "unconnected-(U4-ADC0_DP1-Pad14)") (class "Default")
      (node (ref "U4") (pin "14") (pinfunction "ADC0_DP1_14") (pintype "passive"))
    )
    (net (code "99") (name "unconnected-(U4-ADC1_DM0{slash}ADC0_DM3-Pad21)") (class "Default")
      (node (ref "U4") (pin "21") (pinfunction "ADC1_DM0/ADC0_DM3_21") (pintype "passive"))
    )
    (net (code "100") (name "unconnected-(U4-ADC1_DM1{slash}ADC0_DM2-Pad17)") (class "Default")
      (node (ref "U4") (pin "17") (pinfunction "ADC1_DM1/ADC0_DM2_17") (pintype "passive"))
    )
    (net (code "101") (name "unconnected-(U4-ADC1_DP0{slash}ADC0_DP3-Pad20)") (class "Default")
      (node (ref "U4") (pin "20") (pinfunction "ADC1_DP0/ADC0_DP3_20") (pintype "passive"))
    )
    (net (code "102") (name "unconnected-(U4-ADC1_DP1{slash}ADC0_DP2-Pad16)") (class "Default")
      (node (ref "U4") (pin "16") (pinfunction "ADC1_DP1/ADC0_DP2_16") (pintype "passive"))
    )
    (net (code "103") (name "unconnected-(U4-DAC0_OUT{slash}CMP1_IN3{slash}ADC0_SE23-Pad27)") (class "Default")
      (node (ref "U4") (pin "27") (pinfunction "DAC0_OUT/CMP1_IN3/ADC0_SE23_27") (pintype "passive"))
    )
    (net (code "104") (name "unconnected-(U4-EXTAL32-Pad29)") (class "Default")
      (node (ref "U4") (pin "29") (pinfunction "EXTAL32_29") (pintype "passive"))
    )
    (net (code "105") (name "unconnected-(U4-NC-Pad13)") (class "Default")
      (node (ref "U4") (pin "13") (pinfunction "NC_13") (pintype "passive"))
    )
    (net (code "106") (name "unconnected-(U4-PTA1-Pad35)") (class "Default")
      (node (ref "U4") (pin "35") (pinfunction "PTA1_35") (pintype "passive"))
    )
    (net (code "107") (name "unconnected-(U4-PTA4{slash}LLWU_P3-Pad38)") (class "Default")
      (node (ref "U4") (pin "38") (pinfunction "PTA4/LLWU_P3_38") (pintype "passive"))
    )
    (net (code "108") (name "unconnected-(U4-PTA5-Pad39)") (class "Default")
      (node (ref "U4") (pin "39") (pinfunction "PTA5_39") (pintype "passive"))
    )
    (net (code "109") (name "unconnected-(U4-PTA12-Pad42)") (class "Default")
      (node (ref "U4") (pin "42") (pinfunction "PTA12_42") (pintype "passive"))
    )
    (net (code "110") (name "unconnected-(U4-PTA13{slash}LLWU_P4-Pad43)") (class "Default")
      (node (ref "U4") (pin "43") (pinfunction "PTA13/LLWU_P4_43") (pintype "passive"))
    )
    (net (code "111") (name "unconnected-(U4-PTA14-Pad44)") (class "Default")
      (node (ref "U4") (pin "44") (pinfunction "PTA14_44") (pintype "passive"))
    )
    (net (code "112") (name "unconnected-(U4-PTA15-Pad45)") (class "Default")
      (node (ref "U4") (pin "45") (pinfunction "PTA15_45") (pintype "passive"))
    )
    (net (code "113") (name "unconnected-(U4-PTA16-Pad46)") (class "Default")
      (node (ref "U4") (pin "46") (pinfunction "PTA16_46") (pintype "passive"))
    )
    (net (code "114") (name "unconnected-(U4-PTA17-Pad47)") (class "Default")
      (node (ref "U4") (pin "47") (pinfunction "PTA17_47") (pintype "passive"))
    )
    (net (code "115") (name "unconnected-(U4-PTA18-Pad50)") (class "Default")
      (node (ref "U4") (pin "50") (pinfunction "PTA18_50") (pintype "passive"))
    )
    (net (code "116") (name "unconnected-(U4-PTB1-Pad54)") (class "Default")
      (node (ref "U4") (pin "54") (pinfunction "PTB1_54") (pintype "passive"))
    )
    (net (code "117") (name "unconnected-(U4-PTB2-Pad55)") (class "Default")
      (node (ref "U4") (pin "55") (pinfunction "PTB2_55") (pintype "passive"))
    )
    (net (code "118") (name "unconnected-(U4-PTB3-Pad56)") (class "Default")
      (node (ref "U4") (pin "56") (pinfunction "PTB3_56") (pintype "passive"))
    )
    (net (code "119") (name "unconnected-(U4-PTB21-Pad67)") (class "Default")
      (node (ref "U4") (pin "67") (pinfunction "PTB21_67") (pintype "passive"))
    )
    (net (code "120") (name "unconnected-(U4-PTB22-Pad68)") (class "Default")
      (node (ref "U4") (pin "68") (pinfunction "PTB22_68") (pintype "passive"))
    )
    (net (code "121") (name "unconnected-(U4-PTB23-Pad69)") (class "Default")
      (node (ref "U4") (pin "69") (pinfunction "PTB23_69") (pintype "passive"))
    )
    (net (code "122") (name "unconnected-(U4-PTC0-Pad70)") (class "Default")
      (node (ref "U4") (pin "70") (pinfunction "PTC0_70") (pintype "passive"))
    )
    (net (code "123") (name "unconnected-(U4-PTC2-Pad72)") (class "Default")
      (node (ref "U4") (pin "72") (pinfunction "PTC2_72") (pintype "passive"))
    )
    (net (code "124") (name "unconnected-(U4-PTC14-Pad86)") (class "Default")
      (node (ref "U4") (pin "86") (pinfunction "PTC14_86") (pintype "passive"))
    )
    (net (code "125") (name "unconnected-(U4-PTE0{slash}CLKOUT32K-Pad1)") (class "Default")
      (node (ref "U4") (pin "1") (pinfunction "PTE0/CLKOUT32K_1") (pintype "passive"))
    )
    (net (code "126") (name "unconnected-(U4-PTE4{slash}LLWU_P2-Pad5)") (class "Default")
      (node (ref "U4") (pin "5") (pinfunction "PTE4/LLWU_P2_5") (pintype "passive"))
    )
    (net (code "127") (name "unconnected-(U4-PTE5-Pad6)") (class "Default")
      (node (ref "U4") (pin "6") (pinfunction "PTE5_6") (pintype "passive"))
    )
    (net (code "128") (name "unconnected-(U4-PTE6-Pad7)") (class "Default")
      (node (ref "U4") (pin "7") (pinfunction "PTE6_7") (pintype "passive"))
    )
    (net (code "129") (name "unconnected-(U4-PTE24-Pad31)") (class "Default")
      (node (ref "U4") (pin "31") (pinfunction "PTE24_31") (pintype "passive"))
    )
    (net (code "130") (name "unconnected-(U4-PTE25-Pad32)") (class "Default")
      (node (ref "U4") (pin "32") (pinfunction "PTE25_32") (pintype "passive"))
    )
    (net (code "131") (name "unconnected-(U4-PTE26{slash}CLKOUT32K-Pad33)") (class "Default")
      (node (ref "U4") (pin "33") (pinfunction "PTE26/CLKOUT32K_33") (pintype "passive"))
    )
    (net (code "132") (name "unconnected-(U4-VREF_OUT{slash}CMP1_IN5{slash}CMP0_IN5{slash}ADC1_SE18-Pad26)") (class "Default")
      (node (ref "U4") (pin "26") (pinfunction "VREF_OUT/CMP1_IN5/CMP0_IN5/ADC1_SE18_26") (pintype "passive"))
    )
    (net (code "133") (name "unconnected-(U4-XTAL32-Pad28)") (class "Default")
      (node (ref "U4") (pin "28") (pinfunction "XTAL32_28") (pintype "passive"))
    )
    (net (code "134") (name "unconnected-(U5-NC-Pad5)") (class "Default")
      (node (ref "U5") (pin "5") (pinfunction "NC_5") (pintype "passive"))
    )
    (net (code "135") (name "unconnected-(U5-NC-Pad11)") (class "Default")
      (node (ref "U5") (pin "11") (pinfunction "NC_11") (pintype "passive"))
    )
  )
)
